# ignition3.net
KiCad netlist of a schematic drawn in EAGLE
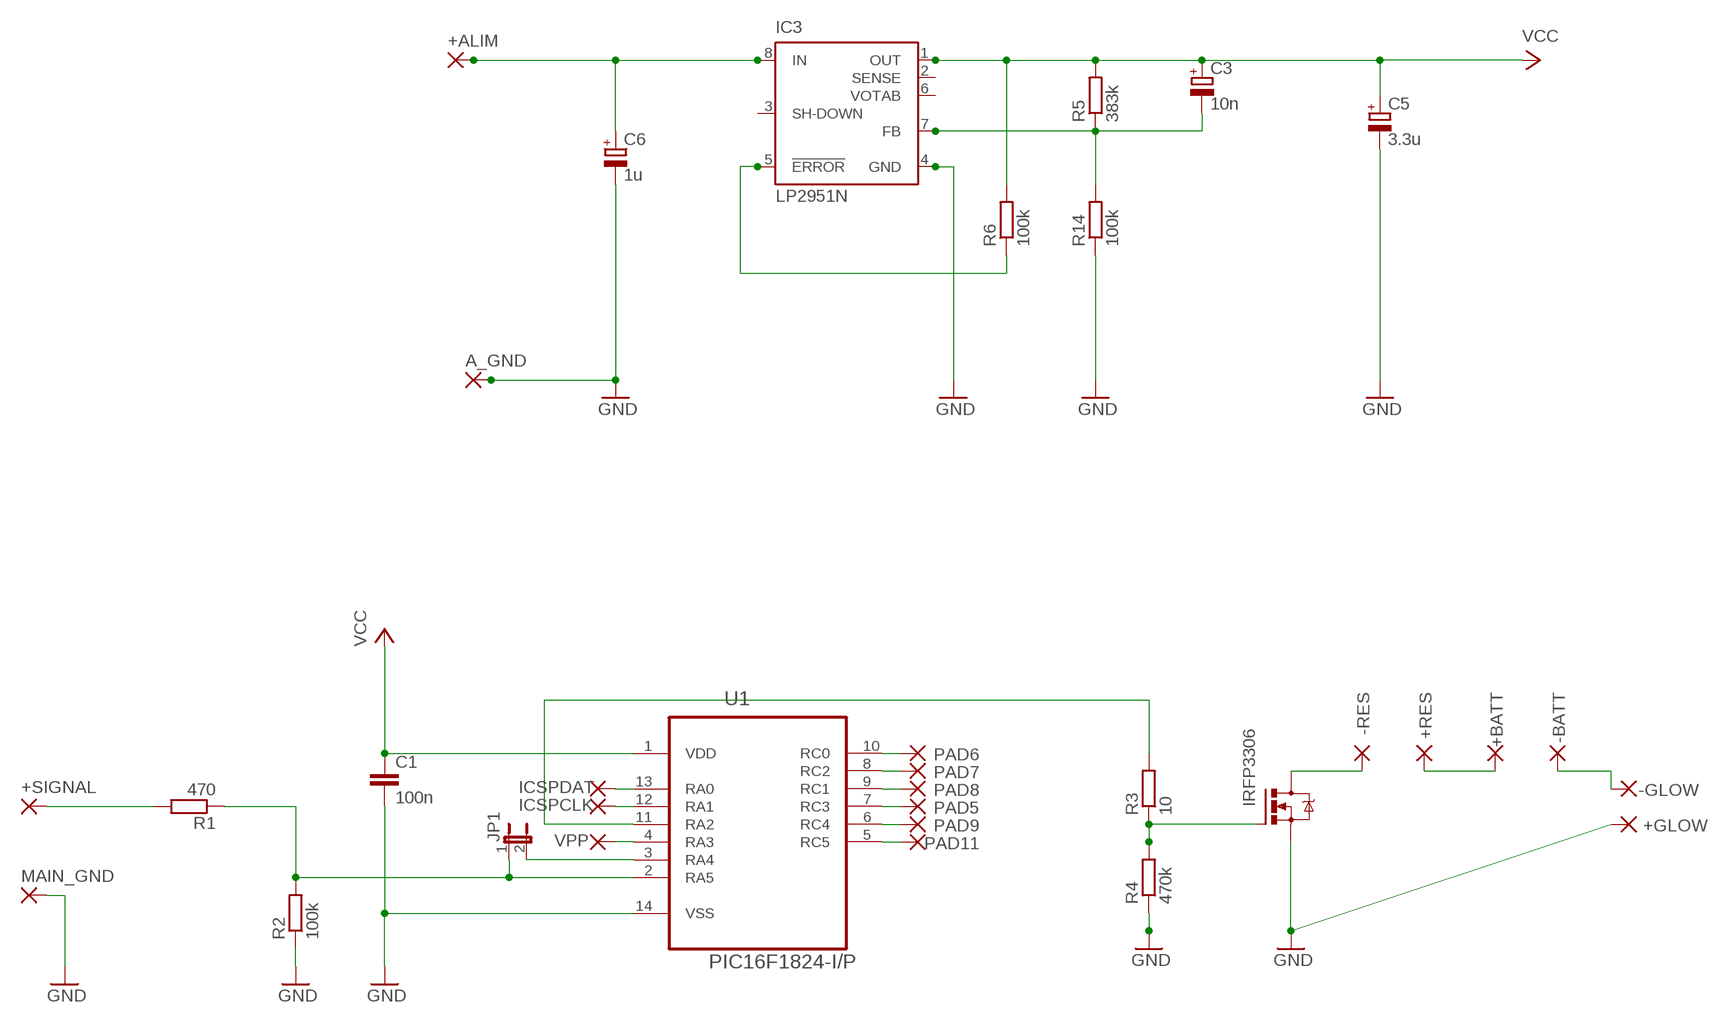
[diagram p0: schematic, sheet 1]

(export (version "E")
  (design (tool "Eeschema 10.0.6"))
  (components
    (comp (ref "+ALIM")
      (value "2,15/1,0")
      (footprint "eagle-import:2,15_1,0")
      (libsource (lib "eagle-import") (part "2,15/1,0"))
    )
    (comp (ref "+BATT")
      (value "WIREPAD3,17/1,3")
      (footprint "eagle-import:3,17_1,3")
      (libsource (lib "eagle-import") (part "WIREPAD3,17/1,3"))
    )
    (comp (ref "+GLOW")
      (value "WIREPAD3,17/1,3")
      (footprint "eagle-import:3,17_1,3")
      (libsource (lib "eagle-import") (part "WIREPAD3,17/1,3"))
    )
    (comp (ref "+RES")
      (value "WIREPAD3,17/1,3")
      (footprint "eagle-import:3,17_1,3")
      (libsource (lib "eagle-import") (part "WIREPAD3,17/1,3"))
    )
    (comp (ref "+SIGNAL")
      (value "2,15/1,0")
      (footprint "eagle-import:2,15_1,0")
      (libsource (lib "eagle-import") (part "2,15/1,0"))
    )
    (comp (ref "-BATT")
      (value "WIREPAD3,17/1,3")
      (footprint "eagle-import:3,17_1,3")
      (libsource (lib "eagle-import") (part "WIREPAD3,17/1,3"))
    )
    (comp (ref "-GLOW")
      (value "WIREPAD3,17/1,3")
      (footprint "eagle-import:3,17_1,3")
      (libsource (lib "eagle-import") (part "WIREPAD3,17/1,3"))
    )
    (comp (ref "-RES")
      (value "WIREPAD3,17/1,3")
      (footprint "eagle-import:3,17_1,3")
      (libsource (lib "eagle-import") (part "WIREPAD3,17/1,3"))
    )
    (comp (ref "A_GND")
      (value "2,15/1,0")
      (footprint "eagle-import:2,15_1,0")
      (libsource (lib "eagle-import") (part "2,15/1,0"))
    )
    (comp (ref "C1")
      (value "100n")
      (footprint "eagle-import:C050-035X075")
      (libsource (lib "eagle-import") (part "C-EU050-035X075"))
    )
    (comp (ref "C3")
      (value "10n")
      (footprint "eagle-import:E5-6")
      (libsource (lib "eagle-import") (part "CPOL-EUE5-6"))
    )
    (comp (ref "C5")
      (value "3.3u")
      (footprint "eagle-import:E2,5-5")
      (libsource (lib "eagle-import") (part "CPOL-EUE2.5-5"))
    )
    (comp (ref "C6")
      (value "1u")
      (footprint "eagle-import:E2,5-5")
      (libsource (lib "eagle-import") (part "CPOL-EUE2.5-5"))
    )
    (comp (ref "IC3")
      (value "LP2951N")
      (footprint "eagle-import:DIL08")
      (libsource (lib "eagle-import") (part "LP2951N"))
    )
    (comp (ref "ICSPCLK")
      (value "2,15/1,0")
      (footprint "eagle-import:2,15_1,0")
      (libsource (lib "eagle-import") (part "2,15/1,0"))
    )
    (comp (ref "ICSPDAT")
      (value "2,15/1,0")
      (footprint "eagle-import:2,15_1,0")
      (libsource (lib "eagle-import") (part "2,15/1,0"))
    )
    (comp (ref "JP1")
      (value "JP1E")
      (footprint "eagle-import:JP1")
      (libsource (lib "eagle-import") (part "JP1E"))
    )
    (comp (ref "MAIN_GND")
      (value "2,15/1,0")
      (footprint "eagle-import:2,15_1,0")
      (libsource (lib "eagle-import") (part "2,15/1,0"))
    )
    (comp (ref "PAD5")
      (value "2,15/1,0")
      (footprint "eagle-import:2,15_1,0")
      (libsource (lib "eagle-import") (part "2,15/1,0"))
    )
    (comp (ref "PAD6")
      (value "2,15/1,0")
      (footprint "eagle-import:2,15_1,0")
      (libsource (lib "eagle-import") (part "2,15/1,0"))
    )
    (comp (ref "PAD7")
      (value "2,15/1,0")
      (footprint "eagle-import:2,15_1,0")
      (libsource (lib "eagle-import") (part "2,15/1,0"))
    )
    (comp (ref "PAD8")
      (value "2,15/1,0")
      (footprint "eagle-import:2,15_1,0")
      (libsource (lib "eagle-import") (part "2,15/1,0"))
    )
    (comp (ref "PAD9")
      (value "2,15/1,0")
      (footprint "eagle-import:2,15_1,0")
      (libsource (lib "eagle-import") (part "2,15/1,0"))
    )
    (comp (ref "PAD11")
      (value "2,15/1,0")
      (footprint "eagle-import:2,15_1,0")
      (libsource (lib "eagle-import") (part "2,15/1,0"))
    )
    (comp (ref "Q2")
      (value "IRFP3306")
      (footprint "eagle-import:TO247BV")
      (libsource (lib "eagle-import") (part "IRFPC40"))
    )
    (comp (ref "R1")
      (value "470")
      (footprint "eagle-import:0207_7")
      (libsource (lib "eagle-import") (part "R-EU_0207/7"))
    )
    (comp (ref "R2")
      (value "100k")
      (footprint "eagle-import:0207_7")
      (libsource (lib "eagle-import") (part "R-EU_0207/7"))
    )
    (comp (ref "R3")
      (value "10")
      (footprint "eagle-import:0207_7")
      (libsource (lib "eagle-import") (part "R-EU_0207/7"))
    )
    (comp (ref "R4")
      (value "470k")
      (footprint "eagle-import:0207_7")
      (libsource (lib "eagle-import") (part "R-EU_0207/7"))
    )
    (comp (ref "R5")
      (value "383k")
      (footprint "eagle-import:0207_7")
      (libsource (lib "eagle-import") (part "R-EU_0207/7"))
    )
    (comp (ref "R6")
      (value "100k")
      (footprint "eagle-import:0207_7")
      (libsource (lib "eagle-import") (part "R-EU_0207/7"))
    )
    (comp (ref "R14")
      (value "100k")
      (footprint "eagle-import:0207_7")
      (libsource (lib "eagle-import") (part "R-EU_0207/7"))
    )
    (comp (ref "U1")
      (value "PIC16F1824-I/P")
      (footprint "eagle-import:DIP254P762X533-14")
      (libsource (lib "eagle-import") (part "PIC16F1824-I/P"))
    )
    (comp (ref "VPP")
      (value "2,15/1,0")
      (footprint "eagle-import:2,15_1,0")
      (libsource (lib "eagle-import") (part "2,15/1,0"))
    )
  )
  (nets
    (net (code "1") (name "GND") (class "Default")
      (node (ref "+GLOW") (pin "1") (pinfunction "P_1") (pintype "passive"))
      (node (ref "A_GND") (pin "1") (pinfunction "P_1") (pintype "passive"))
      (node (ref "C1") (pin "2") (pinfunction "2_2") (pintype "passive"))
      (node (ref "C5") (pin "-") (pinfunction "-_-") (pintype "passive"))
      (node (ref "C6") (pin "-") (pinfunction "-_-") (pintype "passive"))
      (node (ref "IC3") (pin "4") (pinfunction "GND_4") (pintype "power_in"))
      (node (ref "MAIN_GND") (pin "1") (pinfunction "P_1") (pintype "passive"))
      (node (ref "Q2") (pin "S") (pinfunction "S_S") (pintype "passive"))
      (node (ref "R14") (pin "1") (pinfunction "1_1") (pintype "passive"))
      (node (ref "R2") (pin "1") (pinfunction "1_1") (pintype "passive"))
      (node (ref "R4") (pin "1") (pinfunction "1_1") (pintype "passive"))
      (node (ref "U1") (pin "14") (pinfunction "VSS_14") (pintype "power_in"))
    )
    (net (code "2") (name "Net-(+ALIM-P)") (class "Default")
      (node (ref "+ALIM") (pin "1") (pinfunction "P_1") (pintype "passive"))
      (node (ref "C6") (pin "+") (pinfunction "+_+") (pintype "passive"))
      (node (ref "IC3") (pin "8") (pinfunction "IN_8") (pintype "input"))
    )
    (net (code "3") (name "Net-(+BATT-P)") (class "Default")
      (node (ref "+BATT") (pin "1") (pinfunction "P_1") (pintype "passive"))
      (node (ref "+RES") (pin "1") (pinfunction "P_1") (pintype "passive"))
    )
    (net (code "4") (name "Net-(+SIGNAL-P)") (class "Default")
      (node (ref "+SIGNAL") (pin "1") (pinfunction "P_1") (pintype "passive"))
      (node (ref "R1") (pin "2") (pinfunction "2_2") (pintype "passive"))
    )
    (net (code "5") (name "Net-(-BATT-P)") (class "Default")
      (node (ref "-BATT") (pin "1") (pinfunction "P_1") (pintype "passive"))
      (node (ref "-GLOW") (pin "1") (pinfunction "P_1") (pintype "passive"))
    )
    (net (code "6") (name "Net-(-RES-P)") (class "Default")
      (node (ref "-RES") (pin "1") (pinfunction "P_1") (pintype "passive"))
      (node (ref "Q2") (pin "D") (pinfunction "D_D") (pintype "passive"))
    )
    (net (code "7") (name "Net-(IC3-FB)") (class "Default")
      (node (ref "C3") (pin "-") (pinfunction "-_-") (pintype "passive"))
      (node (ref "IC3") (pin "7") (pinfunction "FB_7") (pintype "input"))
      (node (ref "R14") (pin "2") (pinfunction "2_2") (pintype "passive"))
      (node (ref "R5") (pin "1") (pinfunction "1_1") (pintype "passive"))
    )
    (net (code "8") (name "Net-(IC3-~{ERROR})") (class "Default")
      (node (ref "IC3") (pin "5") (pinfunction "~{ERROR}_5") (pintype "output"))
      (node (ref "R6") (pin "1") (pinfunction "1_1") (pintype "passive"))
    )
    (net (code "9") (name "Net-(ICSPCLK-P)") (class "Default")
      (node (ref "ICSPCLK") (pin "1") (pinfunction "P_1") (pintype "passive"))
      (node (ref "U1") (pin "12") (pinfunction "RA1_12") (pintype "bidirectional"))
    )
    (net (code "10") (name "Net-(ICSPDAT-P)") (class "Default")
      (node (ref "ICSPDAT") (pin "1") (pinfunction "P_1") (pintype "passive"))
      (node (ref "U1") (pin "13") (pinfunction "RA0_13") (pintype "bidirectional"))
    )
    (net (code "11") (name "Net-(PAD5-P)") (class "Default")
      (node (ref "PAD5") (pin "1") (pinfunction "P_1") (pintype "passive"))
      (node (ref "U1") (pin "7") (pinfunction "RC3_7") (pintype "bidirectional"))
    )
    (net (code "12") (name "Net-(PAD6-P)") (class "Default")
      (node (ref "PAD6") (pin "1") (pinfunction "P_1") (pintype "passive"))
      (node (ref "U1") (pin "10") (pinfunction "RC0_10") (pintype "bidirectional"))
    )
    (net (code "13") (name "Net-(PAD7-P)") (class "Default")
      (node (ref "PAD7") (pin "1") (pinfunction "P_1") (pintype "passive"))
      (node (ref "U1") (pin "8") (pinfunction "RC2_8") (pintype "bidirectional"))
    )
    (net (code "14") (name "Net-(PAD8-P)") (class "Default")
      (node (ref "PAD8") (pin "1") (pinfunction "P_1") (pintype "passive"))
      (node (ref "U1") (pin "9") (pinfunction "RC1_9") (pintype "bidirectional"))
    )
    (net (code "15") (name "Net-(PAD9-P)") (class "Default")
      (node (ref "PAD9") (pin "1") (pinfunction "P_1") (pintype "passive"))
      (node (ref "U1") (pin "6") (pinfunction "RC4_6") (pintype "bidirectional"))
    )
    (net (code "16") (name "Net-(PAD11-P)") (class "Default")
      (node (ref "PAD11") (pin "1") (pinfunction "P_1") (pintype "passive"))
      (node (ref "U1") (pin "5") (pinfunction "RC5_5") (pintype "bidirectional"))
    )
    (net (code "17") (name "Net-(Q2-PadG)") (class "Default")
      (node (ref "Q2") (pin "G") (pinfunction "G_G") (pintype "passive"))
      (node (ref "R3") (pin "1") (pinfunction "1_1") (pintype "passive"))
      (node (ref "R4") (pin "2") (pinfunction "2_2") (pintype "passive"))
    )
    (net (code "18") (name "Net-(U1-RA2)") (class "Default")
      (node (ref "R3") (pin "2") (pinfunction "2_2") (pintype "passive"))
      (node (ref "U1") (pin "11") (pinfunction "RA2_11") (pintype "bidirectional"))
    )
    (net (code "19") (name "Net-(U1-RA3)") (class "Default")
      (node (ref "U1") (pin "4") (pinfunction "RA3_4") (pintype "input"))
      (node (ref "VPP") (pin "1") (pinfunction "P_1") (pintype "passive"))
    )
    (net (code "20") (name "Net-(U1-RA4)") (class "Default")
      (node (ref "JP1") (pin "2") (pinfunction "2_2") (pintype "passive"))
      (node (ref "U1") (pin "3") (pinfunction "RA4_3") (pintype "bidirectional"))
    )
    (net (code "21") (name "Net-(U1-RA5)") (class "Default")
      (node (ref "JP1") (pin "1") (pinfunction "1_1") (pintype "passive"))
      (node (ref "R1") (pin "1") (pinfunction "1_1") (pintype "passive"))
      (node (ref "R2") (pin "2") (pinfunction "2_2") (pintype "passive"))
      (node (ref "U1") (pin "2") (pinfunction "RA5_2") (pintype "bidirectional"))
    )
    (net (code "22") (name "VCC") (class "Default")
      (node (ref "C1") (pin "1") (pinfunction "1_1") (pintype "passive"))
      (node (ref "C3") (pin "+") (pinfunction "+_+") (pintype "passive"))
      (node (ref "C5") (pin "+") (pinfunction "+_+") (pintype "passive"))
      (node (ref "IC3") (pin "1") (pinfunction "OUT_1") (pintype "input"))
      (node (ref "R5") (pin "2") (pinfunction "2_2") (pintype "passive"))
      (node (ref "R6") (pin "2") (pinfunction "2_2") (pintype "passive"))
      (node (ref "U1") (pin "1") (pinfunction "VDD_1") (pintype "power_in"))
    )
    (net (code "23") (name "unconnected-(IC3-SENSE-Pad2)") (class "Default")
      (node (ref "IC3") (pin "2") (pinfunction "SENSE_2") (pintype "input"))
    )
    (net (code "24") (name "unconnected-(IC3-SH-DOWN-Pad3)") (class "Default")
      (node (ref "IC3") (pin "3") (pinfunction "SH-DOWN_3") (pintype "input"))
    )
    (net (code "25") (name "unconnected-(IC3-VOTAB-Pad6)") (class "Default")
      (node (ref "IC3") (pin "6") (pinfunction "VOTAB_6") (pintype "passive"))
    )
  )
)
